# Shield_INA219.net
KiCad netlist of a schematic drawn in EAGLE
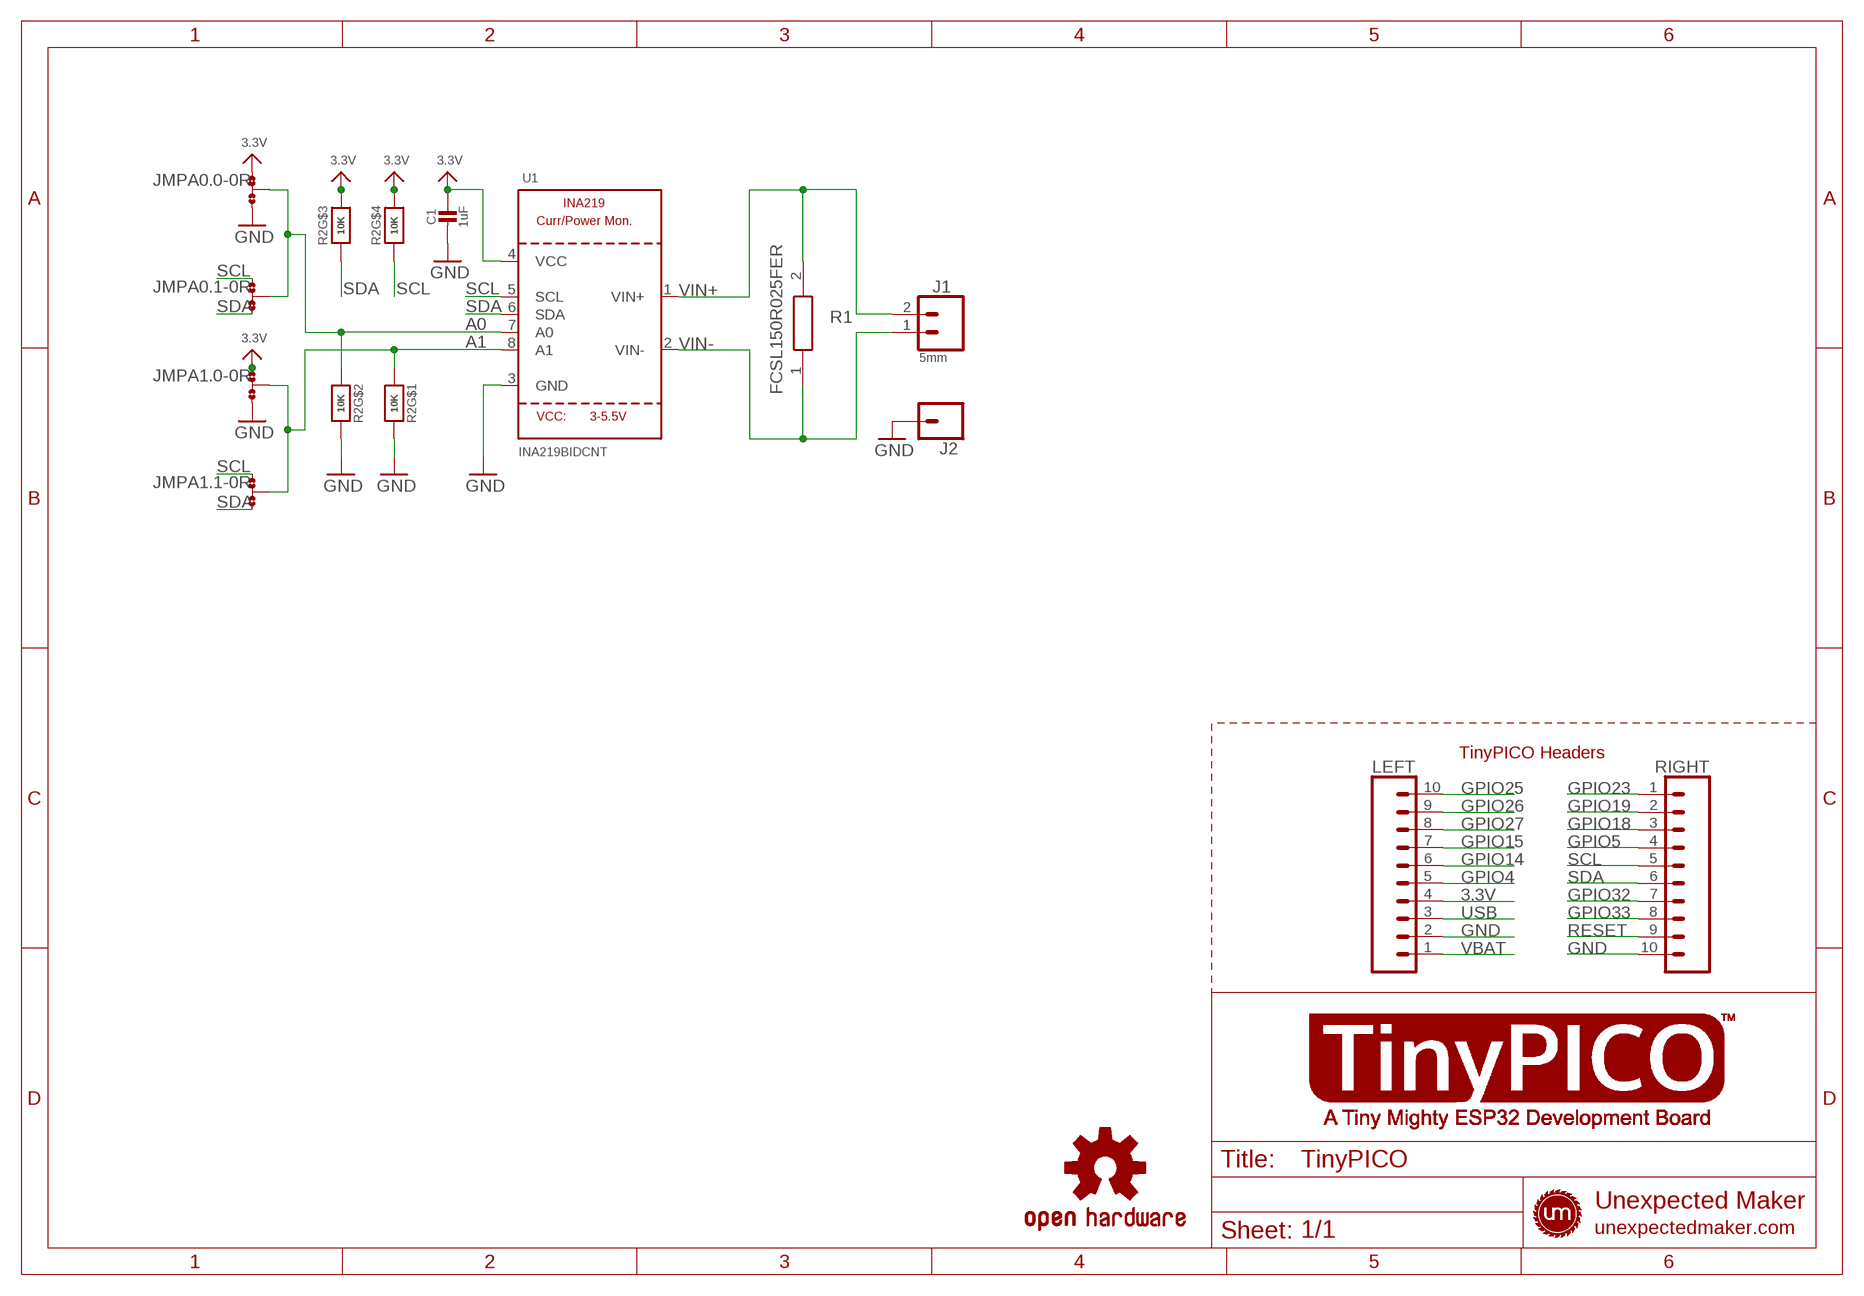
[diagram p0: schematic, sheet 1]

(export (version "E")
  (design (tool "Eeschema 10.0.6"))
  (components
    (comp (ref "C1")
      (value "1uF")
      (footprint "eagle-import:0805-NO@1")
      (libsource (lib "eagle-import") (part "CAP_CERAMIC0805-NOOUTLINE"))
    )
    (comp (ref "J1")
      (value "5mm")
      (footprint "eagle-import:SCREWTERMINAL-5MM-2")
      (libsource (lib "eagle-import") (part "CONN_025MM"))
    )
    (comp (ref "J2")
      (value "CONN_01")
      (footprint "eagle-import:1X01")
      (libsource (lib "eagle-import") (part "CONN_01"))
    )
    (comp (ref "JMPA0.0")
      (value "0R-JUMPD")
      (footprint "eagle-import:C0R-JMP_NONE")
      (libsource (lib "eagle-import") (part "0R-JUMPD"))
    )
    (comp (ref "JMPA0.1")
      (value "0R-JUMPD")
      (footprint "eagle-import:C0R-JMP_NONE")
      (libsource (lib "eagle-import") (part "0R-JUMPD"))
    )
    (comp (ref "JMPA1.0")
      (value "0R-JUMPD")
      (footprint "eagle-import:C0R-JMP_NONE")
      (libsource (lib "eagle-import") (part "0R-JUMPD"))
    )
    (comp (ref "JMPA1.1")
      (value "0R-JUMPD")
      (footprint "eagle-import:C0R-JMP_NONE")
      (libsource (lib "eagle-import") (part "0R-JUMPD"))
    )
    (comp (ref "LEFT")
      (value "TINYPICO_HEADER_10NO_SILK_PTH_FEMALE")
      (footprint "eagle-import:1X10_NO_SILK")
      (libsource (lib "eagle-import") (part "TINYPICO_HEADER_10NO_SILK_PTH_FEMALE"))
    )
    (comp (ref "LOGO1")
      (value "OSHW-LOGOS")
      (footprint "eagle-import:OSHW-LOGO-S")
      (libsource (lib "eagle-import") (part "OSHW-LOGOS"))
    )
    (comp (ref "R1")
      (value "FCSL150R025FER")
      (footprint "eagle-import:RESC90152X87N")
      (libsource (lib "eagle-import") (part "FCSL150R025FER"))
    )
    (comp (ref "R2")
      (value "10K")
      (footprint "eagle-import:RESPACK_4X0603")
      (libsource (lib "eagle-import") (part "RESISTOR_4PACK"))
    )
    (comp (ref "RIGHT")
      (value "TINYPICO_HEADER_10NO_SILK_PTH_FEMALE")
      (footprint "eagle-import:1X10_NO_SILK")
      (libsource (lib "eagle-import") (part "TINYPICO_HEADER_10NO_SILK_PTH_FEMALE"))
    )
    (comp (ref "U1")
      (value "INA219BIDCNT")
      (footprint "eagle-import:SOT23-8")
      (libsource (lib "eagle-import") (part "INA219"))
    )
  )
  (nets
    (net (code "1") (name "/A0") (class "Default")
      (node (ref "JMPA0.0") (pin "2") (pinfunction "2_2") (pintype "passive"))
      (node (ref "JMPA0.1") (pin "2") (pinfunction "2_2") (pintype "passive"))
      (node (ref "R2") (pin "2") (pinfunction "1_2") (pintype "passive"))
      (node (ref "U1") (pin "7") (pinfunction "A0_7") (pintype "bidirectional"))
    )
    (net (code "2") (name "/A1") (class "Default")
      (node (ref "JMPA1.0") (pin "2") (pinfunction "2_2") (pintype "passive"))
      (node (ref "JMPA1.1") (pin "2") (pinfunction "2_2") (pintype "passive"))
      (node (ref "R2") (pin "1") (pinfunction "1_1") (pintype "passive"))
      (node (ref "U1") (pin "8") (pinfunction "A1_8") (pintype "bidirectional"))
    )
    (net (code "3") (name "/GPIO4") (class "Default")
      (node (ref "LEFT") (pin "5") (pinfunction "5_5") (pintype "passive"))
    )
    (net (code "4") (name "/GPIO5") (class "Default")
      (node (ref "RIGHT") (pin "4") (pinfunction "4_4") (pintype "passive"))
    )
    (net (code "5") (name "/GPIO14") (class "Default")
      (node (ref "LEFT") (pin "6") (pinfunction "6_6") (pintype "passive"))
    )
    (net (code "6") (name "/GPIO15") (class "Default")
      (node (ref "LEFT") (pin "7") (pinfunction "7_7") (pintype "passive"))
    )
    (net (code "7") (name "/GPIO18") (class "Default")
      (node (ref "RIGHT") (pin "3") (pinfunction "3_3") (pintype "passive"))
    )
    (net (code "8") (name "/GPIO19") (class "Default")
      (node (ref "RIGHT") (pin "2") (pinfunction "2_2") (pintype "passive"))
    )
    (net (code "9") (name "/GPIO23") (class "Default")
      (node (ref "RIGHT") (pin "1") (pinfunction "1_1") (pintype "passive"))
    )
    (net (code "10") (name "/GPIO25") (class "Default")
      (node (ref "LEFT") (pin "10") (pinfunction "10_10") (pintype "passive"))
    )
    (net (code "11") (name "/GPIO26") (class "Default")
      (node (ref "LEFT") (pin "9") (pinfunction "9_9") (pintype "passive"))
    )
    (net (code "12") (name "/GPIO27") (class "Default")
      (node (ref "LEFT") (pin "8") (pinfunction "8_8") (pintype "passive"))
    )
    (net (code "13") (name "/GPIO32") (class "Default")
      (node (ref "RIGHT") (pin "7") (pinfunction "7_7") (pintype "passive"))
    )
    (net (code "14") (name "/GPIO33") (class "Default")
      (node (ref "RIGHT") (pin "8") (pinfunction "8_8") (pintype "passive"))
    )
    (net (code "15") (name "/RESET") (class "Default")
      (node (ref "RIGHT") (pin "9") (pinfunction "9_9") (pintype "passive"))
    )
    (net (code "16") (name "/SCL") (class "Default")
      (node (ref "JMPA0.1") (pin "1") (pinfunction "1_1") (pintype "passive"))
      (node (ref "JMPA1.1") (pin "1") (pinfunction "1_1") (pintype "passive"))
      (node (ref "R2") (pin "4") (pinfunction "1_4") (pintype "passive"))
      (node (ref "RIGHT") (pin "5") (pinfunction "5_5") (pintype "passive"))
      (node (ref "U1") (pin "5") (pinfunction "SCL_5") (pintype "bidirectional"))
    )
    (net (code "17") (name "/SDA") (class "Default")
      (node (ref "JMPA0.1") (pin "3") (pinfunction "3_3") (pintype "passive"))
      (node (ref "JMPA1.1") (pin "3") (pinfunction "3_3") (pintype "passive"))
      (node (ref "R2") (pin "3") (pinfunction "1_3") (pintype "passive"))
      (node (ref "RIGHT") (pin "6") (pinfunction "6_6") (pintype "passive"))
      (node (ref "U1") (pin "6") (pinfunction "SDA_6") (pintype "bidirectional"))
    )
    (net (code "18") (name "/USB") (class "Default")
      (node (ref "LEFT") (pin "3") (pinfunction "3_3") (pintype "passive"))
    )
    (net (code "19") (name "/VBAT") (class "Default")
      (node (ref "LEFT") (pin "1") (pinfunction "1_1") (pintype "passive"))
    )
    (net (code "20") (name "/VIN+") (class "Default")
      (node (ref "J1") (pin "2") (pinfunction "2_2") (pintype "passive"))
      (node (ref "R1") (pin "2") (pinfunction "2_2") (pintype "bidirectional"))
      (node (ref "U1") (pin "1") (pinfunction "VIN+_1") (pintype "bidirectional"))
    )
    (net (code "21") (name "/VIN-") (class "Default")
      (node (ref "J1") (pin "1") (pinfunction "1_1") (pintype "passive"))
      (node (ref "R1") (pin "1") (pinfunction "1_1") (pintype "bidirectional"))
      (node (ref "U1") (pin "2") (pinfunction "VIN-_2") (pintype "bidirectional"))
    )
    (net (code "22") (name "3.3V") (class "Default")
      (node (ref "C1") (pin "1") (pinfunction "1_1") (pintype "passive"))
      (node (ref "JMPA0.0") (pin "1") (pinfunction "1_1") (pintype "passive"))
      (node (ref "JMPA1.0") (pin "1") (pinfunction "1_1") (pintype "passive"))
      (node (ref "LEFT") (pin "4") (pinfunction "4_4") (pintype "passive"))
      (node (ref "R2") (pin "5") (pinfunction "2_5") (pintype "passive"))
      (node (ref "R2") (pin "6") (pinfunction "2_6") (pintype "passive"))
      (node (ref "U1") (pin "4") (pinfunction "VCC_4") (pintype "power_in"))
    )
    (net (code "23") (name "GND") (class "Default")
      (node (ref "C1") (pin "2") (pinfunction "2_2") (pintype "passive"))
      (node (ref "J2") (pin "1") (pinfunction "1_1") (pintype "passive"))
      (node (ref "JMPA0.0") (pin "3") (pinfunction "3_3") (pintype "passive"))
      (node (ref "JMPA1.0") (pin "3") (pinfunction "3_3") (pintype "passive"))
      (node (ref "LEFT") (pin "2") (pinfunction "2_2") (pintype "passive"))
      (node (ref "R2") (pin "7") (pinfunction "2_7") (pintype "passive"))
      (node (ref "R2") (pin "8") (pinfunction "2_8") (pintype "passive"))
      (node (ref "RIGHT") (pin "10") (pinfunction "10_10") (pintype "passive"))
      (node (ref "U1") (pin "3") (pinfunction "GND_3") (pintype "power_in"))
    )
  )
)
